# UKHASnet-avr-sensor.net
KiCad netlist of a schematic drawn in EAGLE
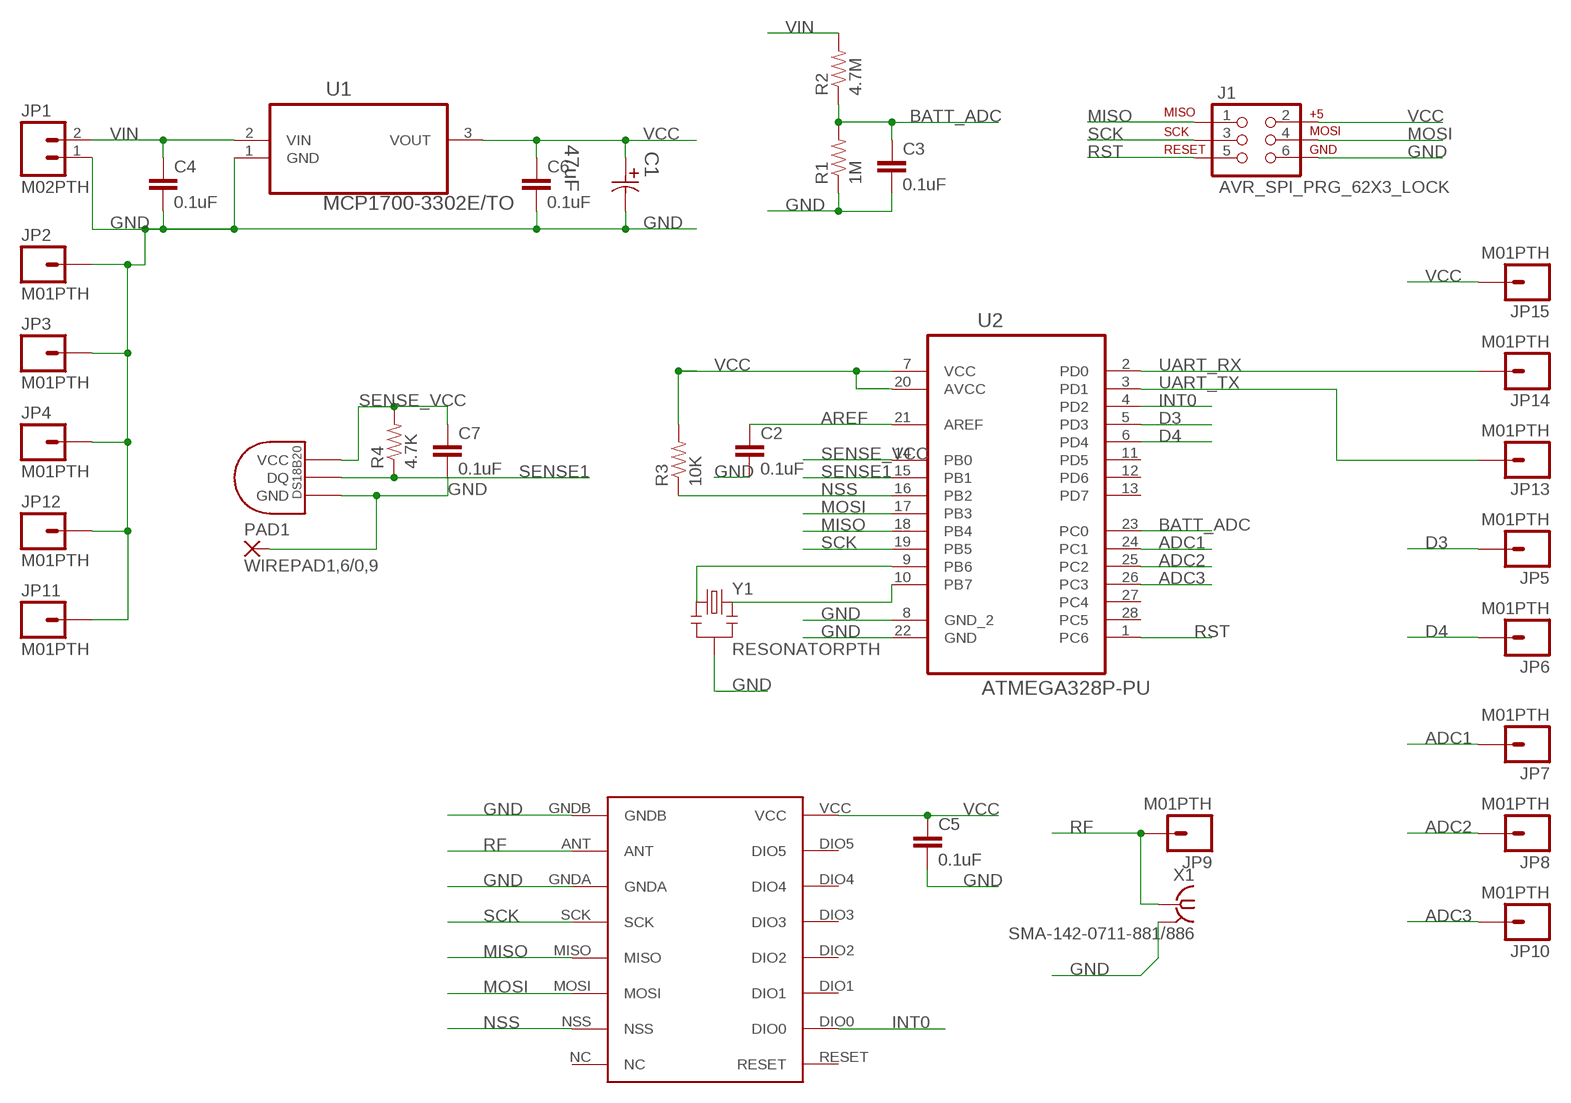
[diagram p0: schematic, sheet 1]

(export (version "E")
  (design (tool "Eeschema 10.0.6"))
  (components
    (comp (ref "C1")
      (value "47uF")
      (footprint "eagle-import:CAPPR150-400X1200")
      (fields (field (name "MPN") "EEUFC1J6R8") (field (name "TOLERANCE") "±20 %"))
      (libsource (lib "eagle-import") (part "EEU-P1.5FC1J6R8"))
    )
    (comp (ref "C2")
      (value "0.1uF")
      (footprint "eagle-import:C2.5-2")
      (libsource (lib "eagle-import") (part "C2.5/2"))
    )
    (comp (ref "C3")
      (value "0.1uF")
      (footprint "eagle-import:C2.5-2")
      (libsource (lib "eagle-import") (part "C2.5/2"))
    )
    (comp (ref "C4")
      (value "0.1uF")
      (footprint "eagle-import:C2.5-2")
      (libsource (lib "eagle-import") (part "C2.5/2"))
    )
    (comp (ref "C5")
      (value "0.1uF")
      (footprint "eagle-import:C2.5-2")
      (libsource (lib "eagle-import") (part "C2.5/2"))
    )
    (comp (ref "C6")
      (value "0.1uF")
      (footprint "eagle-import:C2.5-2")
      (libsource (lib "eagle-import") (part "C2.5/2"))
    )
    (comp (ref "C7")
      (value "0.1uF")
      (footprint "eagle-import:C2.5-2")
      (libsource (lib "eagle-import") (part "C2.5/2"))
    )
    (comp (ref "J1")
      (value "AVR_SPI_PRG_62X3_LOCK")
      (footprint "eagle-import:2X3_LOCK")
      (libsource (lib "eagle-import") (part "AVR_SPI_PRG_62X3_LOCK"))
    )
    (comp (ref "JP1")
      (value "M02PTH")
      (footprint "eagle-import:1X02")
      (libsource (lib "eagle-import") (part "M02PTH"))
    )
    (comp (ref "JP2")
      (value "M01PTH")
      (footprint "eagle-import:1X01")
      (libsource (lib "eagle-import") (part "M01PTH"))
    )
    (comp (ref "JP3")
      (value "M01PTH")
      (footprint "eagle-import:1X01")
      (libsource (lib "eagle-import") (part "M01PTH"))
    )
    (comp (ref "JP4")
      (value "M01PTH")
      (footprint "eagle-import:1X01")
      (libsource (lib "eagle-import") (part "M01PTH"))
    )
    (comp (ref "JP5")
      (value "M01PTH")
      (footprint "eagle-import:1X01")
      (libsource (lib "eagle-import") (part "M01PTH"))
    )
    (comp (ref "JP6")
      (value "M01PTH")
      (footprint "eagle-import:1X01")
      (libsource (lib "eagle-import") (part "M01PTH"))
    )
    (comp (ref "JP7")
      (value "M01PTH")
      (footprint "eagle-import:1X01")
      (libsource (lib "eagle-import") (part "M01PTH"))
    )
    (comp (ref "JP8")
      (value "M01PTH")
      (footprint "eagle-import:1X01")
      (libsource (lib "eagle-import") (part "M01PTH"))
    )
    (comp (ref "JP9")
      (value "M01PTH")
      (footprint "eagle-import:1X01")
      (libsource (lib "eagle-import") (part "M01PTH"))
    )
    (comp (ref "JP10")
      (value "M01PTH")
      (footprint "eagle-import:1X01")
      (libsource (lib "eagle-import") (part "M01PTH"))
    )
    (comp (ref "JP11")
      (value "M01PTH")
      (footprint "eagle-import:1X01")
      (libsource (lib "eagle-import") (part "M01PTH"))
    )
    (comp (ref "JP12")
      (value "M01PTH")
      (footprint "eagle-import:1X01")
      (libsource (lib "eagle-import") (part "M01PTH"))
    )
    (comp (ref "JP13")
      (value "M01PTH")
      (footprint "eagle-import:1X01")
      (libsource (lib "eagle-import") (part "M01PTH"))
    )
    (comp (ref "JP14")
      (value "M01PTH")
      (footprint "eagle-import:1X01")
      (libsource (lib "eagle-import") (part "M01PTH"))
    )
    (comp (ref "JP15")
      (value "M01PTH")
      (footprint "eagle-import:1X01")
      (libsource (lib "eagle-import") (part "M01PTH"))
    )
    (comp (ref "PAD1")
      (value "WIREPAD1,6/0,9")
      (footprint "eagle-import:1,6_0,9")
      (libsource (lib "eagle-import") (part "WIREPAD1,6/0,9"))
    )
    (comp (ref "R1")
      (value "1M")
      (footprint "eagle-import:AXIAL-0.4")
      (libsource (lib "eagle-import") (part "RESISTORPTH-1/4W"))
    )
    (comp (ref "R2")
      (value "4.7M")
      (footprint "eagle-import:AXIAL-0.4")
      (libsource (lib "eagle-import") (part "RESISTORPTH-1/4W"))
    )
    (comp (ref "R3")
      (value "10K")
      (footprint "eagle-import:AXIAL-0.4")
      (libsource (lib "eagle-import") (part "RESISTORPTH-1/4W"))
    )
    (comp (ref "R4")
      (value "4.7K")
      (footprint "eagle-import:AXIAL-0.4")
      (libsource (lib "eagle-import") (part "RESISTORPTH-1/4W"))
    )
    (comp (ref "U$1")
      (value "RFM69HW")
      (footprint "eagle-import:RFM")
      (libsource (lib "eagle-import") (part "RFM69HW"))
    )
    (comp (ref "U$2")
      (value "DS1820TO92")
      (footprint "eagle-import:DS1820")
      (libsource (lib "eagle-import") (part "DS1820TO92"))
    )
    (comp (ref "U1")
      (value "MCP1700-3302E/TO")
      (footprint "eagle-import:TO127P254X495-3")
      (libsource (lib "eagle-import") (part "MCP1700-3302E/TO"))
    )
    (comp (ref "U2")
      (value "ATMEGA328P-PU")
      (footprint "eagle-import:DIP254P762X457-28")
      (libsource (lib "eagle-import") (part "ATMEGA328P-PU"))
    )
    (comp (ref "X1")
      (value "SMA-142-0711-881/886")
      (footprint "eagle-import:J502-ND-142-0711-881_886")
      (fields (field (name "MF") "JOHNSON COMPONENTS") (field (name "MPN") "142-0711-881"))
      (libsource (lib "eagle-import") (part "SMA-142-0711-881/886"))
    )
    (comp (ref "Y1")
      (value "RESONATORPTH")
      (footprint "eagle-import:RESONATOR-PTH")
      (libsource (lib "eagle-import") (part "RESONATORPTH"))
    )
  )
  (nets
    (net (code "1") (name "/ADC1") (class "Default")
      (node (ref "JP7") (pin "1") (pinfunction "1_1") (pintype "passive"))
      (node (ref "U2") (pin "24") (pinfunction "PC1_24") (pintype "bidirectional"))
    )
    (net (code "2") (name "/ADC2") (class "Default")
      (node (ref "JP8") (pin "1") (pinfunction "1_1") (pintype "passive"))
      (node (ref "U2") (pin "25") (pinfunction "PC2_25") (pintype "bidirectional"))
    )
    (net (code "3") (name "/ADC3") (class "Default")
      (node (ref "JP10") (pin "1") (pinfunction "1_1") (pintype "passive"))
      (node (ref "U2") (pin "26") (pinfunction "PC3_26") (pintype "bidirectional"))
    )
    (net (code "4") (name "/AREF") (class "Default")
      (node (ref "C2") (pin "1") (pinfunction "1_1") (pintype "passive"))
      (node (ref "U2") (pin "21") (pinfunction "AREF_21") (pintype "input"))
    )
    (net (code "5") (name "/BATT_ADC") (class "Default")
      (node (ref "C3") (pin "1") (pinfunction "1_1") (pintype "passive"))
      (node (ref "R1") (pin "P$2") (pinfunction "2_P$2") (pintype "passive"))
      (node (ref "R2") (pin "P$1") (pinfunction "1_P$1") (pintype "passive"))
      (node (ref "U2") (pin "23") (pinfunction "PC0_23") (pintype "bidirectional"))
    )
    (net (code "6") (name "/D3") (class "Default")
      (node (ref "JP5") (pin "1") (pinfunction "1_1") (pintype "passive"))
      (node (ref "U2") (pin "5") (pinfunction "PD3_5") (pintype "bidirectional"))
    )
    (net (code "7") (name "/D4") (class "Default")
      (node (ref "JP6") (pin "1") (pinfunction "1_1") (pintype "passive"))
      (node (ref "U2") (pin "6") (pinfunction "PD4_6") (pintype "bidirectional"))
    )
    (net (code "8") (name "/GND") (class "Default")
      (node (ref "C1") (pin "2") (pinfunction "2_2") (pintype "passive"))
      (node (ref "C2") (pin "2") (pinfunction "2_2") (pintype "passive"))
      (node (ref "C3") (pin "2") (pinfunction "2_2") (pintype "passive"))
      (node (ref "C4") (pin "2") (pinfunction "2_2") (pintype "passive"))
      (node (ref "C5") (pin "2") (pinfunction "2_2") (pintype "passive"))
      (node (ref "C6") (pin "2") (pinfunction "2_2") (pintype "passive"))
      (node (ref "C7") (pin "2") (pinfunction "2_2") (pintype "passive"))
      (node (ref "J1") (pin "6") (pinfunction "6_6") (pintype "passive"))
      (node (ref "JP1") (pin "1") (pinfunction "1_1") (pintype "passive"))
      (node (ref "JP11") (pin "1") (pinfunction "1_1") (pintype "passive"))
      (node (ref "JP12") (pin "1") (pinfunction "1_1") (pintype "passive"))
      (node (ref "JP2") (pin "1") (pinfunction "1_1") (pintype "passive"))
      (node (ref "JP3") (pin "1") (pinfunction "1_1") (pintype "passive"))
      (node (ref "JP4") (pin "1") (pinfunction "1_1") (pintype "passive"))
      (node (ref "PAD1") (pin "1") (pinfunction "P_1") (pintype "passive"))
      (node (ref "R1") (pin "P$1") (pinfunction "1_P$1") (pintype "passive"))
      (node (ref "U$1") (pin "GNDA") (pinfunction "GNDA_GNDA") (pintype "bidirectional"))
      (node (ref "U$1") (pin "GNDB") (pinfunction "GNDB_GNDB") (pintype "bidirectional"))
      (node (ref "U$2") (pin "GND") (pinfunction "GND_GND") (pintype "power_in"))
      (node (ref "U1") (pin "1") (pinfunction "GND_1") (pintype "passive"))
      (node (ref "U2") (pin "22") (pinfunction "GND_22") (pintype "passive"))
      (node (ref "U2") (pin "8") (pinfunction "GND_2_8") (pintype "passive"))
      (node (ref "X1") (pin "G@1") (pinfunction "2_G@1") (pintype "passive"))
      (node (ref "X1") (pin "G@2") (pinfunction "2_G@2") (pintype "passive"))
      (node (ref "X1") (pin "G@3") (pinfunction "2_G@3") (pintype "passive"))
      (node (ref "X1") (pin "G@4") (pinfunction "2_G@4") (pintype "passive"))
      (node (ref "Y1") (pin "2") (pinfunction "2_2") (pintype "passive"))
    )
    (net (code "9") (name "/INT0") (class "Default")
      (node (ref "U$1") (pin "DIO0") (pinfunction "DIO0_DIO0") (pintype "bidirectional"))
      (node (ref "U2") (pin "4") (pinfunction "PD2_4") (pintype "bidirectional"))
    )
    (net (code "10") (name "/MISO") (class "Default")
      (node (ref "J1") (pin "1") (pinfunction "1_1") (pintype "passive"))
      (node (ref "U$1") (pin "MISO") (pinfunction "MISO_MISO") (pintype "bidirectional"))
      (node (ref "U2") (pin "18") (pinfunction "PB4_18") (pintype "bidirectional"))
    )
    (net (code "11") (name "/MOSI") (class "Default")
      (node (ref "J1") (pin "4") (pinfunction "4_4") (pintype "passive"))
      (node (ref "U$1") (pin "MOSI") (pinfunction "MOSI_MOSI") (pintype "bidirectional"))
      (node (ref "U2") (pin "17") (pinfunction "PB3_17") (pintype "bidirectional"))
    )
    (net (code "12") (name "/NSS") (class "Default")
      (node (ref "R3") (pin "P$1") (pinfunction "1_P$1") (pintype "passive"))
      (node (ref "U$1") (pin "NSS") (pinfunction "NSS_NSS") (pintype "bidirectional"))
      (node (ref "U2") (pin "16") (pinfunction "PB2_16") (pintype "bidirectional"))
    )
    (net (code "13") (name "/RF") (class "Default")
      (node (ref "JP9") (pin "1") (pinfunction "1_1") (pintype "passive"))
      (node (ref "U$1") (pin "ANT") (pinfunction "ANT_ANT") (pintype "bidirectional"))
      (node (ref "X1") (pin "1") (pinfunction "1_1") (pintype "passive"))
    )
    (net (code "14") (name "/RST") (class "Default")
      (node (ref "J1") (pin "5") (pinfunction "5_5") (pintype "passive"))
      (node (ref "U2") (pin "1") (pinfunction "PC6_1") (pintype "bidirectional"))
    )
    (net (code "15") (name "/SCK") (class "Default")
      (node (ref "J1") (pin "3") (pinfunction "3_3") (pintype "passive"))
      (node (ref "U$1") (pin "SCK") (pinfunction "SCK_SCK") (pintype "bidirectional"))
      (node (ref "U2") (pin "19") (pinfunction "PB5_19") (pintype "bidirectional"))
    )
    (net (code "16") (name "/SENSE1") (class "Default")
      (node (ref "R4") (pin "P$1") (pinfunction "1_P$1") (pintype "passive"))
      (node (ref "U$2") (pin "DQ") (pinfunction "DQ_DQ") (pintype "bidirectional"))
      (node (ref "U2") (pin "15") (pinfunction "PB1_15") (pintype "bidirectional"))
    )
    (net (code "17") (name "/SENSE_VCC") (class "Default")
      (node (ref "C7") (pin "1") (pinfunction "1_1") (pintype "passive"))
      (node (ref "R4") (pin "P$2") (pinfunction "2_P$2") (pintype "passive"))
      (node (ref "U$2") (pin "VDD") (pinfunction "VCC_VDD") (pintype "power_in"))
      (node (ref "U2") (pin "14") (pinfunction "PB0_14") (pintype "bidirectional"))
    )
    (net (code "18") (name "/UART_RX") (class "Default")
      (node (ref "JP14") (pin "1") (pinfunction "1_1") (pintype "passive"))
      (node (ref "U2") (pin "2") (pinfunction "PD0_2") (pintype "bidirectional"))
    )
    (net (code "19") (name "/UART_TX") (class "Default")
      (node (ref "JP13") (pin "1") (pinfunction "1_1") (pintype "passive"))
      (node (ref "U2") (pin "3") (pinfunction "PD1_3") (pintype "bidirectional"))
    )
    (net (code "20") (name "/VCC") (class "Default")
      (node (ref "C1") (pin "1") (pinfunction "1_1") (pintype "passive"))
      (node (ref "C5") (pin "1") (pinfunction "1_1") (pintype "passive"))
      (node (ref "C6") (pin "1") (pinfunction "1_1") (pintype "passive"))
      (node (ref "J1") (pin "2") (pinfunction "2_2") (pintype "passive"))
      (node (ref "JP15") (pin "1") (pinfunction "1_1") (pintype "passive"))
      (node (ref "R3") (pin "P$2") (pinfunction "2_P$2") (pintype "passive"))
      (node (ref "U$1") (pin "VCC") (pinfunction "VCC_VCC") (pintype "bidirectional"))
      (node (ref "U1") (pin "3") (pinfunction "VOUT_3") (pintype "output"))
      (node (ref "U2") (pin "20") (pinfunction "AVCC_20") (pintype "power_in"))
      (node (ref "U2") (pin "7") (pinfunction "VCC_7") (pintype "power_in"))
    )
    (net (code "21") (name "/VIN") (class "Default")
      (node (ref "C4") (pin "1") (pinfunction "1_1") (pintype "passive"))
      (node (ref "JP1") (pin "2") (pinfunction "2_2") (pintype "passive"))
      (node (ref "R2") (pin "P$2") (pinfunction "2_P$2") (pintype "passive"))
      (node (ref "U1") (pin "2") (pinfunction "VIN_2") (pintype "input"))
    )
    (net (code "22") (name "Net-(U2-PB6)") (class "Default")
      (node (ref "U2") (pin "9") (pinfunction "PB6_9") (pintype "bidirectional"))
      (node (ref "Y1") (pin "1") (pinfunction "1_1") (pintype "passive"))
    )
    (net (code "23") (name "Net-(U2-PB7)") (class "Default")
      (node (ref "U2") (pin "10") (pinfunction "PB7_10") (pintype "bidirectional"))
      (node (ref "Y1") (pin "3") (pinfunction "3_3") (pintype "passive"))
    )
    (net (code "24") (name "unconnected-(U$1-PadDIO1)") (class "Default")
      (node (ref "U$1") (pin "DIO1") (pinfunction "DIO1_DIO1") (pintype "bidirectional"))
    )
    (net (code "25") (name "unconnected-(U$1-PadDIO2)") (class "Default")
      (node (ref "U$1") (pin "DIO2") (pinfunction "DIO2_DIO2") (pintype "bidirectional"))
    )
    (net (code "26") (name "unconnected-(U$1-PadDIO3)") (class "Default")
      (node (ref "U$1") (pin "DIO3") (pinfunction "DIO3_DIO3") (pintype "bidirectional"))
    )
    (net (code "27") (name "unconnected-(U$1-PadDIO4)") (class "Default")
      (node (ref "U$1") (pin "DIO4") (pinfunction "DIO4_DIO4") (pintype "bidirectional"))
    )
    (net (code "28") (name "unconnected-(U$1-PadDIO5)") (class "Default")
      (node (ref "U$1") (pin "DIO5") (pinfunction "DIO5_DIO5") (pintype "bidirectional"))
    )
    (net (code "29") (name "unconnected-(U$1-PadNC)") (class "Default")
      (node (ref "U$1") (pin "NC") (pinfunction "NC_NC") (pintype "bidirectional"))
    )
    (net (code "30") (name "unconnected-(U$1-PadRESET)") (class "Default")
      (node (ref "U$1") (pin "RESET") (pinfunction "RESET_RESET") (pintype "bidirectional"))
    )
    (net (code "31") (name "unconnected-(U2-PC4-Pad27)") (class "Default")
      (node (ref "U2") (pin "27") (pinfunction "PC4_27") (pintype "bidirectional"))
    )
    (net (code "32") (name "unconnected-(U2-PC5-Pad28)") (class "Default")
      (node (ref "U2") (pin "28") (pinfunction "PC5_28") (pintype "bidirectional"))
    )
    (net (code "33") (name "unconnected-(U2-PD5-Pad11)") (class "Default")
      (node (ref "U2") (pin "11") (pinfunction "PD5_11") (pintype "bidirectional"))
    )
    (net (code "34") (name "unconnected-(U2-PD6-Pad12)") (class "Default")
      (node (ref "U2") (pin "12") (pinfunction "PD6_12") (pintype "bidirectional"))
    )
    (net (code "35") (name "unconnected-(U2-PD7-Pad13)") (class "Default")
      (node (ref "U2") (pin "13") (pinfunction "PD7_13") (pintype "bidirectional"))
    )
  )
)
